# Regulator_3v3-250mA_MCP1702.net
KiCad netlist of a schematic drawn in Altium Designer
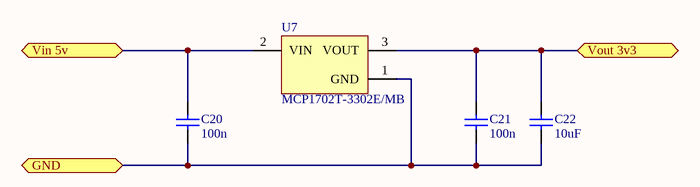
[diagram p0: Regulator 3v3-250mA MCP1702.SchDoc]

(export (version "E")
  (design (tool "Eeschema 10.0.6"))
  (components
    (comp (ref "C20")
      (value "100n")
      (footprint "C0805")
      (fields (field (name "TOLERANCE") "0.1") (field (name "AUTHOR") "Willy Pietersz"))
      (libsource (lib "OurDb") (part "cap_NonPolar"))
    )
    (comp (ref "C21")
      (value "100n")
      (footprint "C0805")
      (fields (field (name "TOLERANCE") "0.1") (field (name "AUTHOR") "Willy Pietersz"))
      (libsource (lib "OurDb") (part "cap_NonPolar"))
    )
    (comp (ref "C22")
      (value "10uF")
      (footprint "C1206")
      (fields
        (field (name "VOLTAGE") "10V")
        (field (name "TOLERANCE") "0.1")
        (field (name "AUTHOR") "Willem Pietersz")
      )
      (libsource (lib "OurDb") (part "cap_NonPolar"))
    )
    (comp (ref "U7")
      (value "MCP1702T-3302E/MB")
      (footprint "SOT-89-MB3_N")
      (fields (field (name "PUBLISHER") "Altium Limited"))
      (libsource (lib "AltiumDatabaseSelection") (part "MCP1702T-3302E/MB"))
    )
  )
  (nets
    (net (code "1") (name "/GND") (class "Default")
      (node (ref "C20") (pin "1") (pinfunction "1_1") (pintype "passive"))
      (node (ref "C21") (pin "1") (pinfunction "1_1") (pintype "passive"))
      (node (ref "C22") (pin "1") (pinfunction "1_1") (pintype "passive"))
      (node (ref "U7") (pin "1") (pinfunction "GND_1") (pintype "power_in"))
    )
    (net (code "2") (name "/Vin 5v") (class "Default")
      (node (ref "C20") (pin "2") (pinfunction "2_2") (pintype "passive"))
      (node (ref "U7") (pin "2") (pinfunction "VIN_2") (pintype "power_in"))
    )
    (net (code "3") (name "/Vout 3v3") (class "Default")
      (node (ref "C21") (pin "2") (pinfunction "2_2") (pintype "passive"))
      (node (ref "C22") (pin "2") (pinfunction "2_2") (pintype "passive"))
      (node (ref "U7") (pin "3") (pinfunction "VOUT_3") (pintype "power_in"))
    )
  )
)
